# 10X_SD_CARD_READER_SCH_SHEET_1.net
KiCad netlist of a schematic drawn in Altium Designer
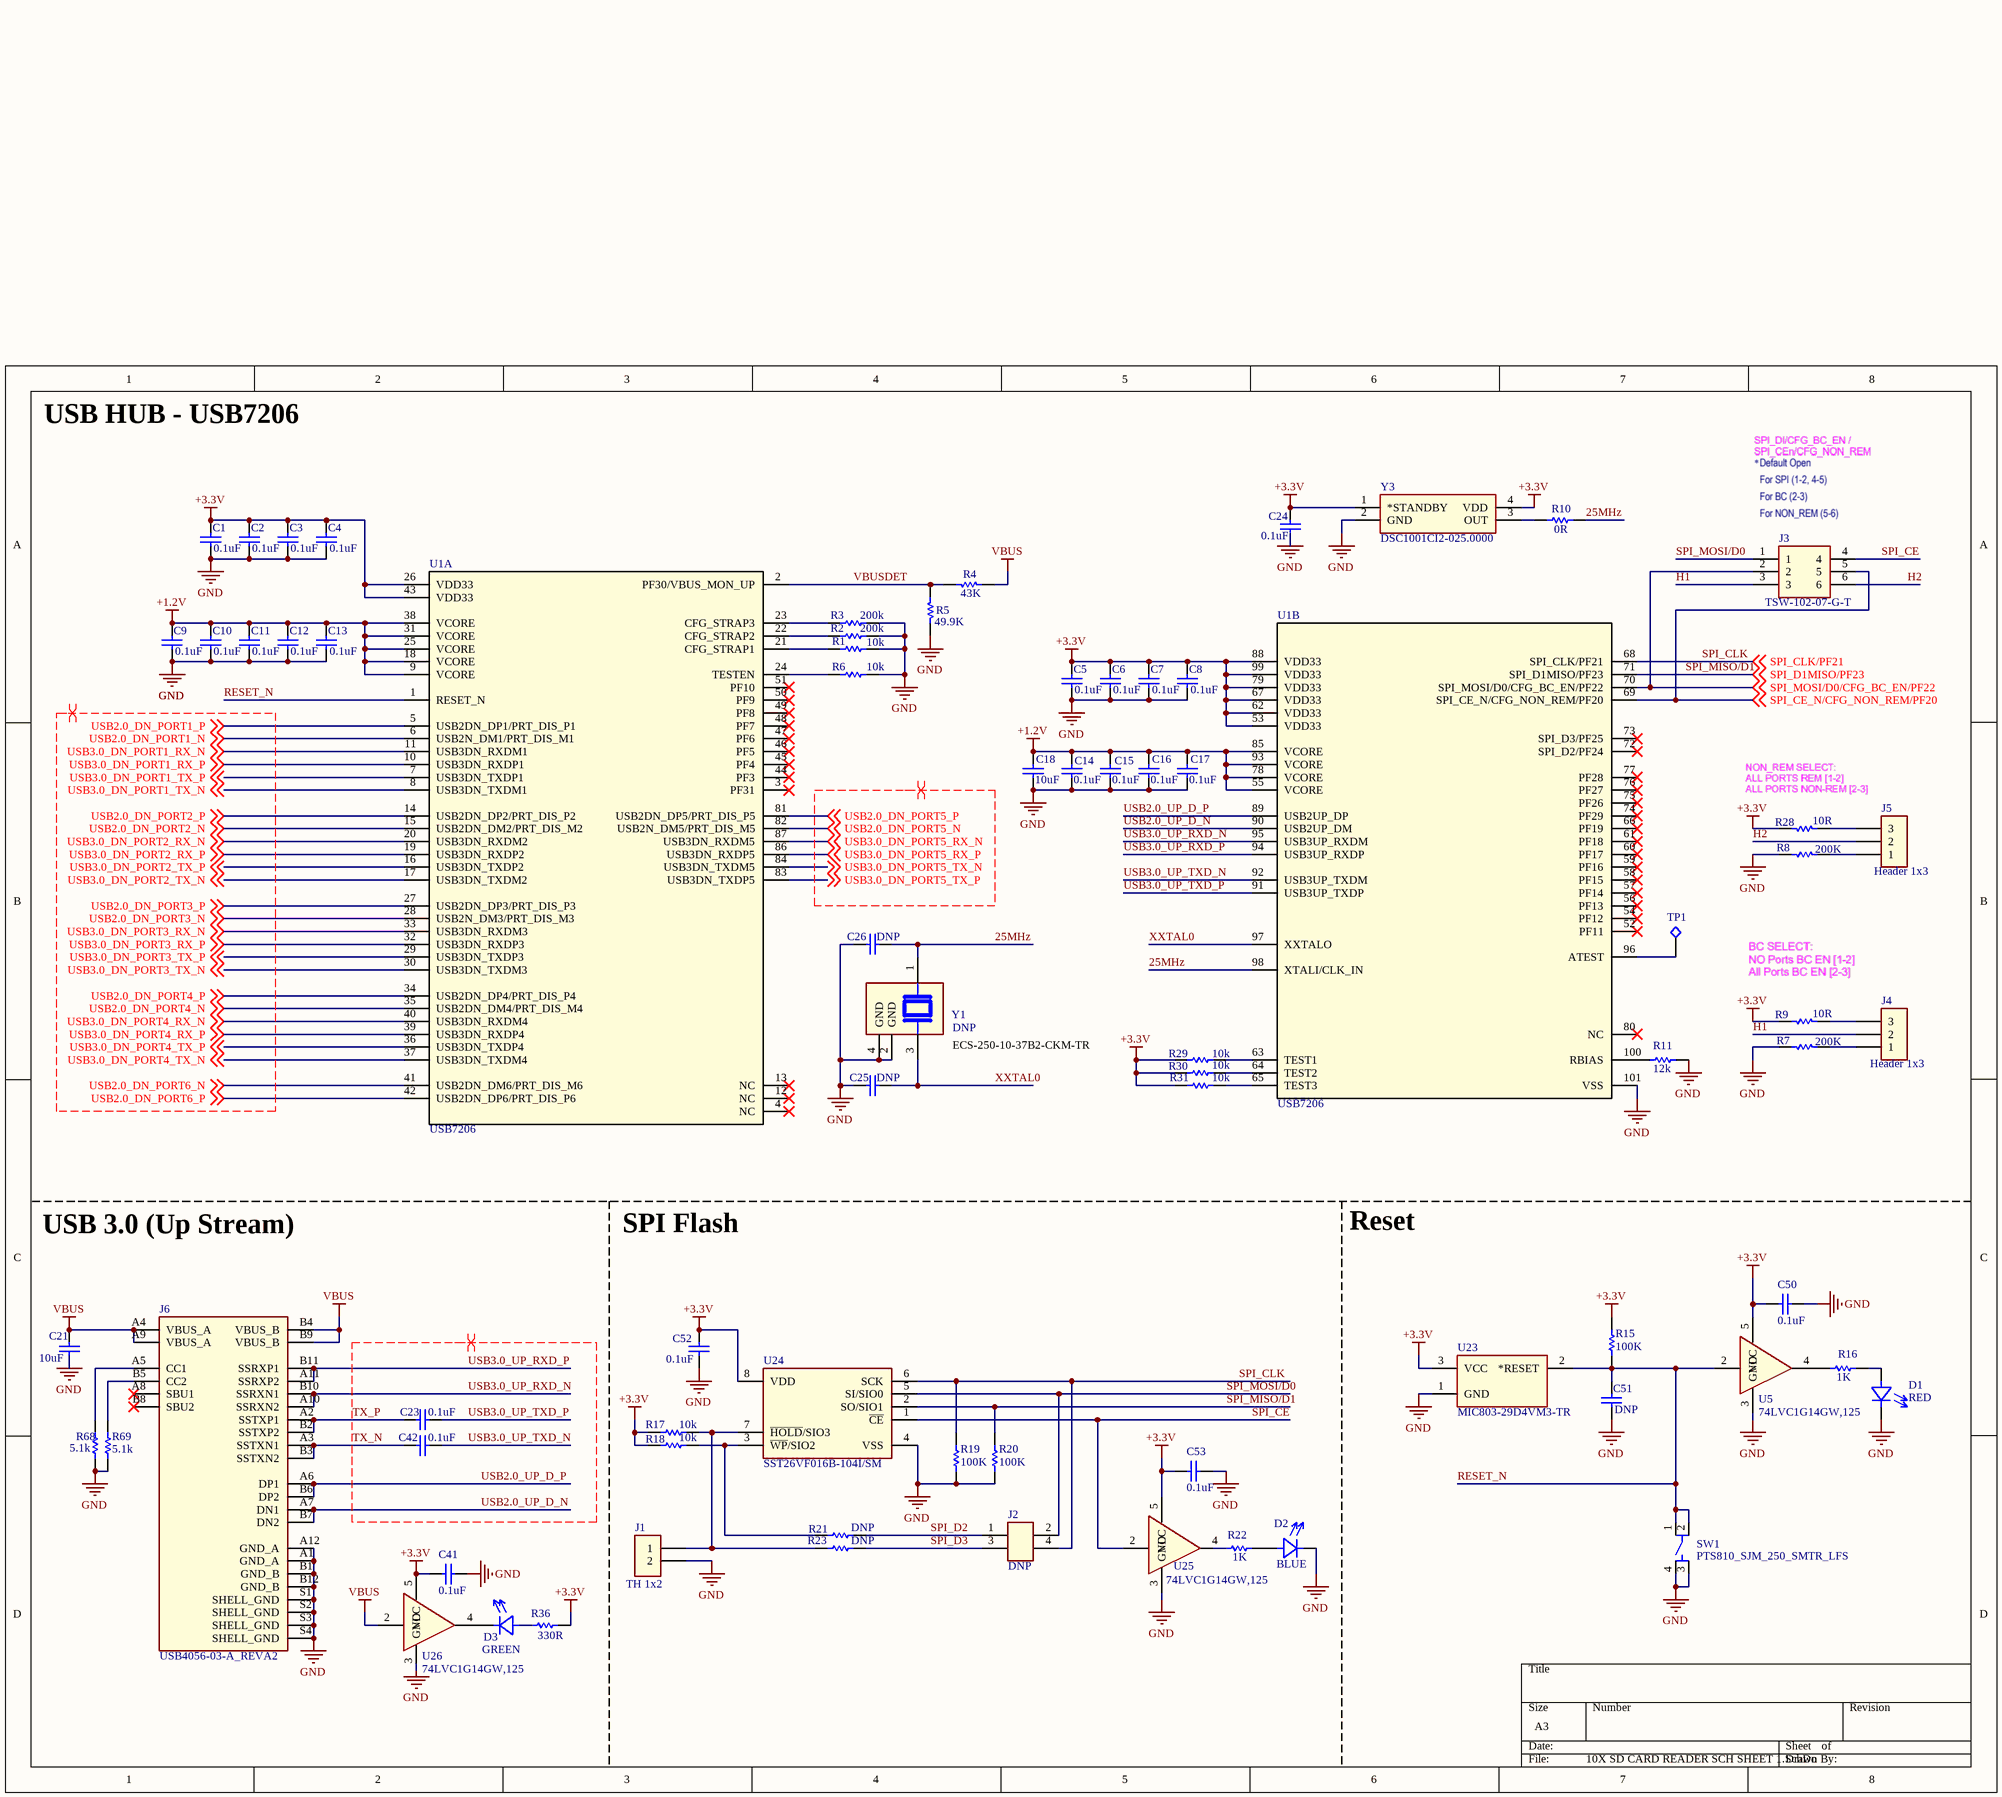
[diagram p0: 10X SD CARD READER SCH SHEET 1.SchDoc]

(export (version "E")
  (design (tool "Eeschema 10.0.6"))
  (components
    (comp (ref "C1")
      (value "0.1uF")
      (footprint "C-0402/1005")
      (description "Capacitor")
      (fields (field (name "PUBLISHER") "Altium Limited"))
      (libsource (lib "Miscellaneous Devices") (part "Cap"))
    )
    (comp (ref "C2")
      (value "0.1uF")
      (footprint "C-0402/1005")
      (description "Capacitor")
      (fields (field (name "PUBLISHER") "Altium Limited"))
      (libsource (lib "Miscellaneous Devices") (part "Cap"))
    )
    (comp (ref "C3")
      (value "0.1uF")
      (footprint "C-0402/1005")
      (description "Capacitor")
      (fields (field (name "PUBLISHER") "Altium Limited"))
      (libsource (lib "Miscellaneous Devices") (part "Cap"))
    )
    (comp (ref "C4")
      (value "0.1uF")
      (footprint "C-0402/1005")
      (description "Capacitor")
      (fields (field (name "PUBLISHER") "Altium Limited"))
      (libsource (lib "Miscellaneous Devices") (part "Cap"))
    )
    (comp (ref "C5")
      (value "0.1uF")
      (footprint "C-0402/1005")
      (description "Capacitor")
      (fields (field (name "PUBLISHER") "Altium Limited"))
      (libsource (lib "Miscellaneous Devices") (part "Cap"))
    )
    (comp (ref "C6")
      (value "0.1uF")
      (footprint "C-0402/1005")
      (description "Capacitor")
      (fields (field (name "PUBLISHER") "Altium Limited"))
      (libsource (lib "Miscellaneous Devices") (part "Cap"))
    )
    (comp (ref "C7")
      (value "0.1uF")
      (footprint "C-0402/1005")
      (description "Capacitor")
      (fields (field (name "PUBLISHER") "Altium Limited"))
      (libsource (lib "Miscellaneous Devices") (part "Cap"))
    )
    (comp (ref "C8")
      (value "0.1uF")
      (footprint "C-0402/1005")
      (description "Capacitor")
      (fields (field (name "PUBLISHER") "Altium Limited"))
      (libsource (lib "Miscellaneous Devices") (part "Cap"))
    )
    (comp (ref "C9")
      (value "0.1uF")
      (footprint "C-0402/1005")
      (description "Capacitor")
      (fields (field (name "PUBLISHER") "Altium Limited"))
      (libsource (lib "Miscellaneous Devices") (part "Cap"))
    )
    (comp (ref "C10")
      (value "0.1uF")
      (footprint "C-0402/1005")
      (description "Capacitor")
      (fields (field (name "PUBLISHER") "Altium Limited"))
      (libsource (lib "Miscellaneous Devices") (part "Cap"))
    )
    (comp (ref "C11")
      (value "0.1uF")
      (footprint "C-0402/1005")
      (description "Capacitor")
      (fields (field (name "PUBLISHER") "Altium Limited"))
      (libsource (lib "Miscellaneous Devices") (part "Cap"))
    )
    (comp (ref "C12")
      (value "0.1uF")
      (footprint "C-0402/1005")
      (description "Capacitor")
      (fields (field (name "PUBLISHER") "Altium Limited"))
      (libsource (lib "Miscellaneous Devices") (part "Cap"))
    )
    (comp (ref "C13")
      (value "0.1uF")
      (footprint "C-0402/1005")
      (description "Capacitor")
      (fields (field (name "PUBLISHER") "Altium Limited"))
      (libsource (lib "Miscellaneous Devices") (part "Cap"))
    )
    (comp (ref "C14")
      (value "0.1uF")
      (footprint "C-0402/1005")
      (description "Capacitor")
      (fields (field (name "PUBLISHER") "Altium Limited"))
      (libsource (lib "Miscellaneous Devices") (part "Cap"))
    )
    (comp (ref "C15")
      (value "0.1uF")
      (footprint "C-0402/1005")
      (description "Capacitor")
      (fields (field (name "PUBLISHER") "Altium Limited"))
      (libsource (lib "Miscellaneous Devices") (part "Cap"))
    )
    (comp (ref "C16")
      (value "0.1uF")
      (footprint "C-0402/1005")
      (description "Capacitor")
      (fields (field (name "PUBLISHER") "Altium Limited"))
      (libsource (lib "Miscellaneous Devices") (part "Cap"))
    )
    (comp (ref "C17")
      (value "0.1uF")
      (footprint "C-0402/1005")
      (description "Capacitor")
      (fields (field (name "PUBLISHER") "Altium Limited"))
      (libsource (lib "Miscellaneous Devices") (part "Cap"))
    )
    (comp (ref "C18")
      (value "10uF")
      (footprint "C-0805/2012")
      (description "Capacitor")
      (fields (field (name "PUBLISHER") "Altium Limited"))
      (libsource (lib "Miscellaneous Devices") (part "Cap"))
    )
    (comp (ref "C21")
      (value "10uF")
      (footprint "C-0805/2012")
      (description "Capacitor")
      (fields (field (name "PUBLISHER") "Altium Limited"))
      (libsource (lib "Miscellaneous Devices") (part "Cap"))
    )
    (comp (ref "C23")
      (value "0.1uF")
      (footprint "C-0402/1005")
      (description "Capacitor")
      (fields (field (name "PUBLISHER") "Altium Limited"))
      (libsource (lib "Miscellaneous Devices") (part "Cap"))
    )
    (comp (ref "C24")
      (value "0.1uF")
      (footprint "C-0402/1005")
      (description "Capacitor")
      (fields (field (name "PUBLISHER") "Altium Limited"))
      (libsource (lib "Miscellaneous Devices") (part "Cap"))
    )
    (comp (ref "C25")
      (value "DNP")
      (footprint "R-0402/1005")
      (description "Capacitor")
      (fields (field (name "PUBLISHER") "Altium Limited"))
      (libsource (lib "Miscellaneous Devices") (part "Cap"))
    )
    (comp (ref "C26")
      (value "DNP")
      (footprint "R-0402/1005")
      (description "Capacitor")
      (fields (field (name "PUBLISHER") "Altium Limited"))
      (libsource (lib "Miscellaneous Devices") (part "Cap"))
    )
    (comp (ref "C41")
      (value "0.1uF")
      (footprint "C-0402/1005")
      (description "Capacitor")
      (fields (field (name "PUBLISHER") "Altium Limited"))
      (libsource (lib "Miscellaneous Devices") (part "Cap"))
    )
    (comp (ref "C42")
      (value "0.1uF")
      (footprint "C-0402/1005")
      (description "Capacitor")
      (fields (field (name "PUBLISHER") "Altium Limited"))
      (libsource (lib "Miscellaneous Devices") (part "Cap"))
    )
    (comp (ref "C50")
      (value "0.1uF")
      (footprint "C-0402/1005")
      (description "Capacitor")
      (fields (field (name "PUBLISHER") "Altium Limited"))
      (libsource (lib "Miscellaneous Devices") (part "Cap"))
    )
    (comp (ref "C51")
      (value "DNP")
      (footprint "C-0402/1005")
      (description "Capacitor")
      (fields (field (name "Comment") "0.1uF") (field (name "PUBLISHER") "Altium Limited"))
      (libsource (lib "Miscellaneous Devices") (part "Cap"))
    )
    (comp (ref "C52")
      (value "0.1uF")
      (footprint "C-0402/1005")
      (description "Capacitor")
      (fields (field (name "PUBLISHER") "Altium Limited"))
      (libsource (lib "Miscellaneous Devices") (part "Cap"))
    )
    (comp (ref "C53")
      (value "0.1uF")
      (footprint "C-0402/1005")
      (description "Capacitor")
      (fields (field (name "PUBLISHER") "Altium Limited"))
      (libsource (lib "Miscellaneous Devices") (part "Cap"))
    )
    (comp (ref "D1")
      (value "RED")
      (footprint "LEDC1608X65N")
      (libsource (lib "Custom_Library") (part "Diode-LED"))
    )
    (comp (ref "D2")
      (value "BLUE")
      (footprint "LEDC1608X65N")
      (libsource (lib "Custom_Library") (part "Diode-LED"))
    )
    (comp (ref "D3")
      (value "GREEN")
      (footprint "LEDC1608X65N")
      (libsource (lib "Custom_Library") (part "Diode-LED"))
    )
    (comp (ref "J1")
      (value "TH 1x2")
      (footprint "PIN HEADER 1x2 2.54mm")
      (description "CONN HEADER VERT 3POS 2.54MM")
      (fields (field (name "MFR. PART NO.") "75160-156-03LF"))
      (libsource (lib "Custom_Library") (part "Header 1x2"))
    )
    (comp (ref "J2")
      (value "DNP")
      (footprint "PIN HEADER 2x2 2.54mm")
      (description "FIXED IND 22UH 620MA 350 MOHM")
      (fields (field (name "MFR. PART NO.") "PH2-04-UA"))
      (libsource (lib "Custom_Library") (part "Header 2x2"))
    )
    (comp (ref "J3")
      (value "TSW-102-07-G-T")
      (footprint "CON6_3X2_TU_TSW_SAI")
      (description "No Description Available")
      (fields (field (name "COPYRIGHT") "Copyright (C) 2023 Ultra Librarian. All rights reserved."))
      (libsource (lib "TSW-102-07-G-T") (part "TSW-102-07-G-T"))
    )
    (comp (ref "J4")
      (value "Header 1x3")
      (footprint "PIN HEADER 1x3 2.54mm")
      (description "CONN HEADER VERT 3POS 2.54MM")
      (fields (field (name "MFR. PART NO.") "75160-156-03LF"))
      (libsource (lib "Custom_Library") (part "Header 1x3"))
    )
    (comp (ref "J5")
      (value "Header 1x3")
      (footprint "PIN HEADER 1x3 2.54mm")
      (description "CONN HEADER VERT 3POS 2.54MM")
      (fields (field (name "MFR. PART NO.") "75160-156-03LF"))
      (libsource (lib "Custom_Library") (part "Header 1x3"))
    )
    (comp (ref "J6")
      (value "USB4056-03-A_REVA2")
      (footprint "GCT_USB4056-03-A_REVA2")
      (fields (field (name "MF") "Global Connector Technology") (field (name "MP") "USB4056-03-A"))
      (libsource (lib "USB4056-03-A_REVA2") (part "USB4056-03-A_REVA2"))
    )
    (comp (ref "R1")
      (value "10k")
      (footprint "R-0402/1005")
      (description "Resistor")
      (fields (field (name "PUBLISHER") "Altium Limited"))
      (libsource (lib "Miscellaneous Devices") (part "Res1"))
    )
    (comp (ref "R2")
      (value "200k")
      (footprint "R-0402/1005")
      (description "Resistor")
      (fields (field (name "PUBLISHER") "Altium Limited"))
      (libsource (lib "Miscellaneous Devices") (part "Res1"))
    )
    (comp (ref "R3")
      (value "200k")
      (footprint "R-0402/1005")
      (description "Resistor")
      (fields (field (name "PUBLISHER") "Altium Limited"))
      (libsource (lib "Miscellaneous Devices") (part "Res1"))
    )
    (comp (ref "R4")
      (value "43K")
      (footprint "R-0402/1005")
      (description "Resistor")
      (fields (field (name "PUBLISHER") "Altium Limited"))
      (libsource (lib "Miscellaneous Devices") (part "Res1"))
    )
    (comp (ref "R5")
      (value "49.9K")
      (footprint "R-0402/1005")
      (description "Resistor")
      (fields (field (name "PUBLISHER") "Altium Limited"))
      (libsource (lib "Miscellaneous Devices") (part "Res1"))
    )
    (comp (ref "R6")
      (value "10k")
      (footprint "R-0402/1005")
      (description "Resistor")
      (fields (field (name "PUBLISHER") "Altium Limited"))
      (libsource (lib "Miscellaneous Devices") (part "Res1"))
    )
    (comp (ref "R7")
      (value "200K")
      (footprint "R-0402/1005")
      (description "Resistor")
      (fields (field (name "PUBLISHER") "Altium Limited"))
      (libsource (lib "Miscellaneous Devices") (part "Res1"))
    )
    (comp (ref "R8")
      (value "200K")
      (footprint "R-0402/1005")
      (description "Resistor")
      (fields (field (name "PUBLISHER") "Altium Limited"))
      (libsource (lib "Miscellaneous Devices") (part "Res1"))
    )
    (comp (ref "R9")
      (value "10R")
      (footprint "R-0402/1005")
      (description "Resistor")
      (fields (field (name "PUBLISHER") "Altium Limited"))
      (libsource (lib "Miscellaneous Devices") (part "Res1"))
    )
    (comp (ref "R10")
      (value "0R")
      (footprint "R-0402/1005")
      (description "Resistor")
      (fields (field (name "PUBLISHER") "Altium Limited"))
      (libsource (lib "Miscellaneous Devices") (part "Res1"))
    )
    (comp (ref "R11")
      (value "12k")
      (footprint "R-0402/1005")
      (description "Resistor")
      (fields (field (name "PUBLISHER") "Altium Limited"))
      (libsource (lib "Miscellaneous Devices") (part "Res1"))
    )
    (comp (ref "R15")
      (value "100K")
      (footprint "R-0402/1005")
      (description "Resistor")
      (fields (field (name "PUBLISHER") "Altium Limited"))
      (libsource (lib "Miscellaneous Devices") (part "Res1"))
    )
    (comp (ref "R16")
      (value "1K")
      (footprint "R-0402/1005")
      (description "Resistor")
      (fields (field (name "PUBLISHER") "Altium Limited"))
      (libsource (lib "Miscellaneous Devices") (part "Res1"))
    )
    (comp (ref "R17")
      (value "10k")
      (footprint "R-0402/1005")
      (description "Resistor")
      (fields (field (name "PUBLISHER") "Altium Limited"))
      (libsource (lib "Miscellaneous Devices") (part "Res1"))
    )
    (comp (ref "R18")
      (value "10k")
      (footprint "R-0402/1005")
      (description "Resistor")
      (fields (field (name "PUBLISHER") "Altium Limited"))
      (libsource (lib "Miscellaneous Devices") (part "Res1"))
    )
    (comp (ref "R19")
      (value "100K")
      (footprint "R-0402/1005")
      (description "Resistor")
      (fields (field (name "PUBLISHER") "Altium Limited"))
      (libsource (lib "Miscellaneous Devices") (part "Res1"))
    )
    (comp (ref "R20")
      (value "100K")
      (footprint "R-0402/1005")
      (description "Resistor")
      (fields (field (name "PUBLISHER") "Altium Limited"))
      (libsource (lib "Miscellaneous Devices") (part "Res1"))
    )
    (comp (ref "R21")
      (value "DNP")
      (footprint "R-0402/1005")
      (description "Resistor")
      (fields (field (name "PUBLISHER") "Altium Limited"))
      (libsource (lib "Miscellaneous Devices") (part "Res1"))
    )
    (comp (ref "R22")
      (value "1K")
      (footprint "R-0402/1005")
      (description "Resistor")
      (fields (field (name "PUBLISHER") "Altium Limited"))
      (libsource (lib "Miscellaneous Devices") (part "Res1"))
    )
    (comp (ref "R23")
      (value "DNP")
      (footprint "R-0402/1005")
      (description "Resistor")
      (fields (field (name "PUBLISHER") "Altium Limited"))
      (libsource (lib "Miscellaneous Devices") (part "Res1"))
    )
    (comp (ref "R28")
      (value "10R")
      (footprint "R-0402/1005")
      (description "Resistor")
      (fields (field (name "PUBLISHER") "Altium Limited"))
      (libsource (lib "Miscellaneous Devices") (part "Res1"))
    )
    (comp (ref "R29")
      (value "10k")
      (footprint "R-0402/1005")
      (description "Resistor")
      (fields (field (name "PUBLISHER") "Altium Limited"))
      (libsource (lib "Miscellaneous Devices") (part "Res1"))
    )
    (comp (ref "R30")
      (value "10k")
      (footprint "R-0402/1005")
      (description "Resistor")
      (fields (field (name "PUBLISHER") "Altium Limited"))
      (libsource (lib "Miscellaneous Devices") (part "Res1"))
    )
    (comp (ref "R31")
      (value "10k")
      (footprint "R-0402/1005")
      (description "Resistor")
      (fields (field (name "PUBLISHER") "Altium Limited"))
      (libsource (lib "Miscellaneous Devices") (part "Res1"))
    )
    (comp (ref "R36")
      (value "330R")
      (footprint "R-0402/1005")
      (description "Resistor")
      (fields (field (name "PUBLISHER") "Altium Limited"))
      (libsource (lib "Miscellaneous Devices") (part "Res1"))
    )
    (comp (ref "R68")
      (value "5.1k")
      (footprint "R-0402/1005")
      (description "Resistor")
      (fields (field (name "PUBLISHER") "Altium Limited"))
      (libsource (lib "Miscellaneous Devices") (part "Res1"))
    )
    (comp (ref "R69")
      (value "5.1k")
      (footprint "R-0402/1005")
      (description "Resistor")
      (fields (field (name "PUBLISHER") "Altium Limited"))
      (libsource (lib "Miscellaneous Devices") (part "Res1"))
    )
    (comp (ref "SW1")
      (value "PTS810_SJM_250_SMTR_LFS")
      (footprint "SW_PTS810_SJM_250_SMTR_LFS")
      (description "Tactile Switch SPST-NO Top Actuated Surface Mount")
      (fields (field (name "MF") "C&K") (field (name "MP") "PTS810 SJM 250 SMTR LFS"))
      (libsource (lib "PTS810_SJM_250_SMTR_LFS") (part "PTS810_SJM_250_SMTR_LFS"))
    )
    (comp (ref "TP1")
      (value "Test Points")
      (footprint "Test Point TH Round H0.9,D1.6")
      (libsource (lib "Custom_Library") (part "Test Points"))
    )
    (comp (ref "U1")
      (value "USB7206")
      (footprint "USB7206")
      (description "IC USB3.1 GEN2 HUB TYPE C")
      (fields
        (field (name "MANUFACTURER") "Microchip Technology")
        (field (name "DIGI-KEY PART NUMBER") "150-USB7206CT-I/KDXTR-ND")
      )
      (libsource (lib "10X SD CARD READER SCH LIB") (part "USB7206"))
    )
    (comp (ref "U5")
      (value "74LVC1G14GW,125")
      (footprint "SOT65P212X110-5N")
      (description "Inverter Schmitt Trigger 1-Element CMOS 5-Pin TSSOP T/R")
      (libsource (lib "74LVC1G14GW,125") (part "74LVC1G14GW,125"))
    )
    (comp (ref "U23")
      (value "MIC803-29D4VM3-TR")
      (footprint "SOT-23_M3_MCH")
      (description "No Description Available")
      (fields (field (name "COPYRIGHT") "Copyright (C) 2023 Ultra Librarian. All rights reserved."))
      (libsource (lib "MIC803-29D4VM3-TR") (part "MIC803-29D4VM3-TR"))
    )
    (comp (ref "U24")
      (value "SST26VF016B-104I/SM")
      (footprint "SOIC127P794X203-8N")
      (libsource (lib "10X SD CARD READER SCH LIB") (part "SST26VF016B-104I/SM"))
    )
    (comp (ref "U25")
      (value "74LVC1G14GW,125")
      (footprint "SOT65P212X110-5N")
      (description "Inverter Schmitt Trigger 1-Element CMOS 5-Pin TSSOP T/R")
      (libsource (lib "74LVC1G14GW,125") (part "74LVC1G14GW,125"))
    )
    (comp (ref "U26")
      (value "74LVC1G14GW,125")
      (footprint "SOT65P212X110-5N")
      (description "Inverter Schmitt Trigger 1-Element CMOS 5-Pin TSSOP T/R")
      (libsource (lib "74LVC1G14GW,125") (part "74LVC1G14GW,125"))
    )
    (comp (ref "Y1")
      (value "DNP")
      (footprint "ECS-250-10-37B2")
      (libsource (lib "10X SD CARD READER SCH LIB") (part "ECS-250-10-37B2-CKM-TR"))
    )
    (comp (ref "Y3")
      (value "DSC1001CI2-025.0000")
      (footprint "CDFN4_3P2X2P5_MCH")
      (description "No Description Available")
      (fields (field (name "COPYRIGHT") "Copyright (C) 2023 Ultra Librarian. All rights reserved."))
      (libsource (lib "DSC1001CI2-025P0000") (part "DSC1001CI2-025.0000"))
    )
  )
  (nets
    (net (code "1") (name "+1.2V") (class "Default")
      (node (ref "C10") (pin "2") (pinfunction "2_2") (pintype "passive"))
      (node (ref "C11") (pin "2") (pinfunction "2_2") (pintype "passive"))
      (node (ref "C12") (pin "2") (pinfunction "2_2") (pintype "passive"))
      (node (ref "C13") (pin "2") (pinfunction "2_2") (pintype "passive"))
      (node (ref "C14") (pin "1") (pinfunction "1_1") (pintype "passive"))
      (node (ref "C15") (pin "1") (pinfunction "1_1") (pintype "passive"))
      (node (ref "C16") (pin "2") (pinfunction "2_2") (pintype "passive"))
      (node (ref "C17") (pin "2") (pinfunction "2_2") (pintype "passive"))
      (node (ref "C18") (pin "2") (pinfunction "2_2") (pintype "passive"))
      (node (ref "C9") (pin "2") (pinfunction "2_2") (pintype "passive"))
      (node (ref "U1") (pin "18") (pinfunction "VCORE_18") (pintype "passive"))
      (node (ref "U1") (pin "25") (pinfunction "VCORE_25") (pintype "passive"))
      (node (ref "U1") (pin "31") (pinfunction "VCORE_31") (pintype "passive"))
      (node (ref "U1") (pin "38") (pinfunction "VCORE_38") (pintype "passive"))
      (node (ref "U1") (pin "55") (pinfunction "VCORE_55") (pintype "passive"))
      (node (ref "U1") (pin "78") (pinfunction "VCORE_78") (pintype "passive"))
      (node (ref "U1") (pin "85") (pinfunction "VCORE_85") (pintype "passive"))
      (node (ref "U1") (pin "9") (pinfunction "VCORE_9") (pintype "passive"))
      (node (ref "U1") (pin "93") (pinfunction "VCORE_93") (pintype "passive"))
    )
    (net (code "2") (name "+3.3V") (class "Default")
      (node (ref "C1") (pin "2") (pinfunction "2_2") (pintype "passive"))
      (node (ref "C2") (pin "2") (pinfunction "2_2") (pintype "passive"))
      (node (ref "C24") (pin "2") (pinfunction "2_2") (pintype "passive"))
      (node (ref "C3") (pin "2") (pinfunction "2_2") (pintype "passive"))
      (node (ref "C4") (pin "2") (pinfunction "2_2") (pintype "passive"))
      (node (ref "C41") (pin "2") (pinfunction "2_2") (pintype "passive"))
      (node (ref "C5") (pin "2") (pinfunction "2_2") (pintype "passive"))
      (node (ref "C50") (pin "2") (pinfunction "2_2") (pintype "passive"))
      (node (ref "C52") (pin "2") (pinfunction "2_2") (pintype "passive"))
      (node (ref "C53") (pin "2") (pinfunction "2_2") (pintype "passive"))
      (node (ref "C6") (pin "2") (pinfunction "2_2") (pintype "passive"))
      (node (ref "C7") (pin "2") (pinfunction "2_2") (pintype "passive"))
      (node (ref "C8") (pin "2") (pinfunction "2_2") (pintype "passive"))
      (node (ref "R15") (pin "1") (pinfunction "1_1") (pintype "passive"))
      (node (ref "R17") (pin "2") (pinfunction "2_2") (pintype "passive"))
      (node (ref "R18") (pin "2") (pinfunction "2_2") (pintype "passive"))
      (node (ref "R28") (pin "2") (pinfunction "2_2") (pintype "passive"))
      (node (ref "R29") (pin "2") (pinfunction "2_2") (pintype "passive"))
      (node (ref "R30") (pin "2") (pinfunction "2_2") (pintype "passive"))
      (node (ref "R31") (pin "2") (pinfunction "2_2") (pintype "passive"))
      (node (ref "R36") (pin "2") (pinfunction "2_2") (pintype "passive"))
      (node (ref "R9") (pin "2") (pinfunction "2_2") (pintype "passive"))
      (node (ref "U1") (pin "26") (pinfunction "VDD33_26") (pintype "passive"))
      (node (ref "U1") (pin "43") (pinfunction "VDD33_43") (pintype "passive"))
      (node (ref "U1") (pin "53") (pinfunction "VDD33_53") (pintype "passive"))
      (node (ref "U1") (pin "62") (pinfunction "VDD33_62") (pintype "passive"))
      (node (ref "U1") (pin "67") (pinfunction "VDD33_67") (pintype "passive"))
      (node (ref "U1") (pin "79") (pinfunction "VDD33_79") (pintype "passive"))
      (node (ref "U1") (pin "88") (pinfunction "VDD33_88") (pintype "passive"))
      (node (ref "U1") (pin "99") (pinfunction "VDD33_99") (pintype "passive"))
      (node (ref "U23") (pin "3") (pinfunction "VCC_3") (pintype "power_in"))
      (node (ref "U24") (pin "8") (pinfunction "VDD_8") (pintype "passive"))
      (node (ref "U25") (pin "5") (pinfunction "VCC_5") (pintype "passive"))
      (node (ref "U26") (pin "5") (pinfunction "VCC_5") (pintype "passive"))
      (node (ref "U5") (pin "5") (pinfunction "VCC_5") (pintype "passive"))
      (node (ref "Y3") (pin "1") (pinfunction "*STANDBY_1") (pintype "passive"))
      (node (ref "Y3") (pin "4") (pinfunction "VDD_4") (pintype "passive"))
    )
    (net (code "3") (name "/25MHz") (class "Default")
      (node (ref "C26") (pin "1") (pinfunction "1_1") (pintype "passive"))
      (node (ref "R10") (pin "2") (pinfunction "2_2") (pintype "passive"))
      (node (ref "U1") (pin "98") (pinfunction "XTALI/CLK_IN_98") (pintype "passive"))
      (node (ref "Y1") (pin "1") (pinfunction "1_1") (pintype "passive"))
    )
    (net (code "4") (name "/H1") (class "Default")
      (node (ref "J3") (pin "3") (pinfunction "3_3") (pintype "passive"))
      (node (ref "J4") (pin "2") (pinfunction "2_2") (pintype "passive"))
    )
    (net (code "5") (name "/H2") (class "Default")
      (node (ref "J3") (pin "6") (pinfunction "6_6") (pintype "passive"))
      (node (ref "J5") (pin "2") (pinfunction "2_2") (pintype "passive"))
    )
    (net (code "6") (name "/RESET_N") (class "Default")
      (node (ref "C51") (pin "2") (pinfunction "2_2") (pintype "passive"))
      (node (ref "R15") (pin "2") (pinfunction "2_2") (pintype "passive"))
      (node (ref "SW1") (pin "1") (pinfunction "1_1") (pintype "passive"))
      (node (ref "SW1") (pin "2") (pinfunction "2_2") (pintype "passive"))
      (node (ref "U1") (pin "1") (pinfunction "RESET_N_1") (pintype "passive"))
      (node (ref "U23") (pin "2") (pinfunction "*RESET_2") (pintype "passive"))
      (node (ref "U5") (pin "2") (pinfunction "A_2") (pintype "passive"))
    )
    (net (code "7") (name "/SPI_CE") (class "Default")
      (node (ref "J3") (pin "4") (pinfunction "4_4") (pintype "passive"))
      (node (ref "U24") (pin "1") (pinfunction "~{CE}_1") (pintype "passive"))
      (node (ref "U25") (pin "2") (pinfunction "A_2") (pintype "passive"))
    )
    (net (code "8") (name "/SPI_D2") (class "Default")
      (node (ref "J2") (pin "1") (pinfunction "1_1") (pintype "passive"))
      (node (ref "R21") (pin "2") (pinfunction "2_2") (pintype "passive"))
    )
    (net (code "9") (name "/SPI_D3") (class "Default")
      (node (ref "J2") (pin "3") (pinfunction "3_3") (pintype "passive"))
      (node (ref "R23") (pin "2") (pinfunction "2_2") (pintype "passive"))
    )
    (net (code "10") (name "/SPI_MOSI{slash}D0") (class "Default")
      (node (ref "J2") (pin "2") (pinfunction "2_2") (pintype "passive"))
      (node (ref "J3") (pin "1") (pinfunction "1_1") (pintype "passive"))
      (node (ref "U24") (pin "5") (pinfunction "SI/SIO0_5") (pintype "passive"))
    )
    (net (code "11") (name "/TX_N") (class "Default")
      (node (ref "C42") (pin "2") (pinfunction "2_2") (pintype "passive"))
      (node (ref "J6") (pin "A3") (pinfunction "SSTXN1_A3") (pintype "passive"))
      (node (ref "J6") (pin "B3") (pinfunction "SSTXN2_B3") (pintype "passive"))
    )
    (net (code "12") (name "/TX_P") (class "Default")
      (node (ref "C23") (pin "2") (pinfunction "2_2") (pintype "passive"))
      (node (ref "J6") (pin "A2") (pinfunction "SSTXP1_A2") (pintype "passive"))
      (node (ref "J6") (pin "B2") (pinfunction "SSTXP2_B2") (pintype "passive"))
    )
    (net (code "13") (name "/USB2.0_UP_D_N") (class "Default")
      (node (ref "J6") (pin "A7") (pinfunction "DN1_A7") (pintype "passive"))
      (node (ref "J6") (pin "B7") (pinfunction "DN2_B7") (pintype "passive"))
      (node (ref "U1") (pin "90") (pinfunction "USB2UP_DM_90") (pintype "passive"))
    )
    (net (code "14") (name "/USB2.0_UP_D_P") (class "Default")
      (node (ref "J6") (pin "A6") (pinfunction "DP1_A6") (pintype "passive"))
      (node (ref "J6") (pin "B6") (pinfunction "DP2_B6") (pintype "passive"))
      (node (ref "U1") (pin "89") (pinfunction "USB2UP_DP_89") (pintype "passive"))
    )
    (net (code "15") (name "/USB3.0_UP_RXD_N") (class "Default")
      (node (ref "J6") (pin "A10") (pinfunction "SSRXN2_A10") (pintype "passive"))
      (node (ref "J6") (pin "B10") (pinfunction "SSRXN1_B10") (pintype "passive"))
      (node (ref "U1") (pin "95") (pinfunction "USB3UP_RXDM_95") (pintype "passive"))
    )
    (net (code "16") (name "/USB3.0_UP_RXD_P") (class "Default")
      (node (ref "J6") (pin "A11") (pinfunction "SSRXP2_A11") (pintype "passive"))
      (node (ref "J6") (pin "B11") (pinfunction "SSRXP1_B11") (pintype "passive"))
      (node (ref "U1") (pin "94") (pinfunction "USB3UP_RXDP_94") (pintype "passive"))
    )
    (net (code "17") (name "/USB3.0_UP_TXD_N") (class "Default")
      (node (ref "C42") (pin "1") (pinfunction "1_1") (pintype "passive"))
      (node (ref "U1") (pin "92") (pinfunction "USB3UP_TXDM_92") (pintype "passive"))
    )
    (net (code "18") (name "/USB3.0_UP_TXD_P") (class "Default")
      (node (ref "C23") (pin "1") (pinfunction "1_1") (pintype "passive"))
      (node (ref "U1") (pin "91") (pinfunction "USB3UP_TXDP_91") (pintype "passive"))
    )
    (net (code "19") (name "/VBUSDET") (class "Default")
      (node (ref "R4") (pin "1") (pinfunction "1_1") (pintype "passive"))
      (node (ref "R5") (pin "1") (pinfunction "1_1") (pintype "passive"))
      (node (ref "U1") (pin "2") (pinfunction "PF30/VBUS_MON_UP_2") (pintype "passive"))
    )
    (net (code "20") (name "/XXTAL0") (class "Default")
      (node (ref "C25") (pin "1") (pinfunction "1_1") (pintype "passive"))
      (node (ref "U1") (pin "97") (pinfunction "XXTALO_97") (pintype "passive"))
      (node (ref "Y1") (pin "3") (pinfunction "2_3") (pintype "passive"))
    )
    (net (code "21") (name "GND") (class "Default")
      (node (ref "C1") (pin "1") (pinfunction "1_1") (pintype "passive"))
      (node (ref "C10") (pin "1") (pinfunction "1_1") (pintype "passive"))
      (node (ref "C11") (pin "1") (pinfunction "1_1") (pintype "passive"))
      (node (ref "C12") (pin "1") (pinfunction "1_1") (pintype "passive"))
      (node (ref "C13") (pin "1") (pinfunction "1_1") (pintype "passive"))
      (node (ref "C14") (pin "2") (pinfunction "2_2") (pintype "passive"))
      (node (ref "C15") (pin "2") (pinfunction "2_2") (pintype "passive"))
      (node (ref "C16") (pin "1") (pinfunction "1_1") (pintype "passive"))
      (node (ref "C17") (pin "1") (pinfunction "1_1") (pintype "passive"))
      (node (ref "C18") (pin "1") (pinfunction "1_1") (pintype "passive"))
      (node (ref "C2") (pin "1") (pinfunction "1_1") (pintype "passive"))
      (node (ref "C21") (pin "1") (pinfunction "1_1") (pintype "passive"))
      (node (ref "C24") (pin "1") (pinfunction "1_1") (pintype "passive"))
      (node (ref "C25") (pin "2") (pinfunction "2_2") (pintype "passive"))
      (node (ref "C26") (pin "2") (pinfunction "2_2") (pintype "passive"))
      (node (ref "C3") (pin "1") (pinfunction "1_1") (pintype "passive"))
      (node (ref "C4") (pin "1") (pinfunction "1_1") (pintype "passive"))
      (node (ref "C41") (pin "1") (pinfunction "1_1") (pintype "passive"))
      (node (ref "C5") (pin "1") (pinfunction "1_1") (pintype "passive"))
      (node (ref "C50") (pin "1") (pinfunction "1_1") (pintype "passive"))
      (node (ref "C51") (pin "1") (pinfunction "1_1") (pintype "passive"))
      (node (ref "C52") (pin "1") (pinfunction "1_1") (pintype "passive"))
      (node (ref "C53") (pin "1") (pinfunction "1_1") (pintype "passive"))
      (node (ref "C6") (pin "1") (pinfunction "1_1") (pintype "passive"))
      (node (ref "C7") (pin "1") (pinfunction "1_1") (pintype "passive"))
      (node (ref "C8") (pin "1") (pinfunction "1_1") (pintype "passive"))
      (node (ref "C9") (pin "1") (pinfunction "1_1") (pintype "passive"))
      (node (ref "D1") (pin "C") (pinfunction "C_C") (pintype "passive"))
      (node (ref "D2") (pin "C") (pinfunction "C_C") (pintype "passive"))
      (node (ref "J1") (pin "2") (pinfunction "2_2") (pintype "passive"))
      (node (ref "J6") (pin "A1") (pinfunction "GND_A_A1") (pintype "passive"))
      (node (ref "J6") (pin "A12") (pinfunction "GND_A_A12") (pintype "passive"))
      (node (ref "J6") (pin "B1") (pinfunction "GND_B_B1") (pintype "passive"))
      (node (ref "J6") (pin "B12") (pinfunction "GND_B_B12") (pintype "passive"))
      (node (ref "J6") (pin "S1") (pinfunction "SHELL_GND_S1") (pintype "passive"))
      (node (ref "J6") (pin "S2") (pinfunction "SHELL_GND_S2") (pintype "passive"))
      (node (ref "J6") (pin "S3") (pinfunction "SHELL_GND_S3") (pintype "passive"))
      (node (ref "J6") (pin "S4") (pinfunction "SHELL_GND_S4") (pintype "passive"))
      (node (ref "R1") (pin "2") (pinfunction "2_2") (pintype "passive"))
      (node (ref "R11") (pin "1") (pinfunction "1_1") (pintype "passive"))
      (node (ref "R19") (pin "2") (pinfunction "2_2") (pintype "passive"))
      (node (ref "R2") (pin "2") (pinfunction "2_2") (pintype "passive"))
      (node (ref "R20") (pin "2") (pinfunction "2_2") (pintype "passive"))
      (node (ref "R3") (pin "2") (pinfunction "2_2") (pintype "passive"))
      (node (ref "R5") (pin "2") (pinfunction "2_2") (pintype "passive"))
      (node (ref "R6") (pin "1") (pinfunction "1_1") (pintype "passive"))
      (node (ref "R68") (pin "1") (pinfunction "1_1") (pintype "passive"))
      (node (ref "R69") (pin "1") (pinfunction "1_1") (pintype "passive"))
      (node (ref "R7") (pin "1") (pinfunction "1_1") (pintype "passive"))
      (node (ref "R8") (pin "1") (pinfunction "1_1") (pintype "passive"))
      (node (ref "SW1") (pin "3") (pinfunction "3_3") (pintype "passive"))
      (node (ref "SW1") (pin "4") (pinfunction "4_4") (pintype "passive"))
      (node (ref "U1") (pin "101") (pinfunction "VSS_101") (pintype "passive"))
      (node (ref "U23") (pin "1") (pinfunction "GND_1") (pintype "power_in"))
      (node (ref "U24") (pin "4") (pinfunction "VSS_4") (pintype "passive"))
      (node (ref "U25") (pin "3") (pinfunction "GND_3") (pintype "passive"))
      (node (ref "U26") (pin "3") (pinfunction "GND_3") (pintype "passive"))
      (node (ref "U5") (pin "3") (pinfunction "GND_3") (pintype "passive"))
      (node (ref "Y1") (pin "2") (pinfunction "GND_2") (pintype "power_in"))
      (node (ref "Y1") (pin "4") (pinfunction "GND_4") (pintype "power_in"))
      (node (ref "Y3") (pin "2") (pinfunction "GND_2") (pintype "passive"))
    )
    (net (code "22") (name "Net-(D1-PadA)") (class "Default")
      (node (ref "D1") (pin "A") (pinfunction "A_A") (pintype "passive"))
      (node (ref "R16") (pin "1") (pinfunction "1_1") (pintype "passive"))
    )
    (net (code "23") (name "Net-(D2-PadA)") (class "Default")
      (node (ref "D2") (pin "A") (pinfunction "A_A") (pintype "passive"))
      (node (ref "R22") (pin "1") (pinfunction "1_1") (pintype "passive"))
    )
    (net (code "24") (name "Net-(D3-PadA)") (class "Default")
      (node (ref "D3") (pin "A") (pinfunction "A_A") (pintype "passive"))
      (node (ref "R36") (pin "1") (pinfunction "1_1") (pintype "passive"))
    )
    (net (code "25") (name "Net-(J4-Pad1)") (class "Default")
      (node (ref "J4") (pin "1") (pinfunction "1_1") (pintype "passive"))
      (node (ref "R7") (pin "2") (pinfunction "2_2") (pintype "passive"))
    )
    (net (code "26") (name "Net-(J4-Pad3)") (class "Default")
      (node (ref "J4") (pin "3") (pinfunction "3_3") (pintype "passive"))
      (node (ref "R9") (pin "1") (pinfunction "1_1") (pintype "passive"))
    )
    (net (code "27") (name "Net-(J5-Pad1)") (class "Default")
      (node (ref "J5") (pin "1") (pinfunction "1_1") (pintype "passive"))
      (node (ref "R8") (pin "2") (pinfunction "2_2") (pintype "passive"))
    )
    (net (code "28") (name "Net-(J5-Pad3)") (class "Default")
      (node (ref "J5") (pin "3") (pinfunction "3_3") (pintype "passive"))
      (node (ref "R28") (pin "1") (pinfunction "1_1") (pintype "passive"))
    )
    (net (code "29") (name "Net-(J6-CC1)") (class "Default")
      (node (ref "J6") (pin "A5") (pinfunction "CC1_A5") (pintype "passive"))
      (node (ref "R68") (pin "2") (pinfunction "2_2") (pintype "passive"))
    )
    (net (code "30") (name "Net-(J6-CC2)") (class "Default")
      (node (ref "J6") (pin "B5") (pinfunction "CC2_B5") (pintype "passive"))
      (node (ref "R69") (pin "2") (pinfunction "2_2") (pintype "passive"))
    )
    (net (code "31") (name "Net-(U1A-CFG_STRAP1)") (class "Default")
      (node (ref "R1") (pin "1") (pinfunction "1_1") (pintype "passive"))
      (node (ref "U1") (pin "21") (pinfunction "CFG_STRAP1_21") (pintype "passive"))
    )
    (net (code "32") (name "Net-(U1A-CFG_STRAP2)") (class "Default")
      (node (ref "R2") (pin "1") (pinfunction "1_1") (pintype "passive"))
      (node (ref "U1") (pin "22") (pinfunction "CFG_STRAP2_22") (pintype "passive"))
    )
    (net (code "33") (name "Net-(U1A-CFG_STRAP3)") (class "Default")
      (node (ref "R3") (pin "1") (pinfunction "1_1") (pintype "passive"))
      (node (ref "U1") (pin "23") (pinfunction "CFG_STRAP3_23") (pintype "passive"))
    )
    (net (code "34") (name "Net-(U1A-TESTEN)") (class "Default")
      (node (ref "R6") (pin "2") (pinfunction "2_2") (pintype "passive"))
      (node (ref "U1") (pin "24") (pinfunction "TESTEN_24") (pintype "passive"))
    )
    (net (code "35") (name "Net-(U1B-ATEST)") (class "Default")
      (node (ref "TP1") (pin "1") (pinfunction "1_1") (pintype "passive"))
      (node (ref "U1") (pin "96") (pinfunction "ATEST_96") (pintype "passive"))
    )
    (net (code "36") (name "Net-(U1B-RBIAS)") (class "Default")
      (node (ref "R11") (pin "2") (pinfunction "2_2") (pintype "passive"))
      (node (ref "U1") (pin "100") (pinfunction "RBIAS_100") (pintype "passive"))
    )
    (net (code "37") (name "Net-(U1B-TEST1)") (class "Default")
      (node (ref "R29") (pin "1") (pinfunction "1_1") (pintype "passive"))
      (node (ref "U1") (pin "63") (pinfunction "TEST1_63") (pintype "passive"))
    )
    (net (code "38") (name "Net-(U1B-TEST2)") (class "Default")
      (node (ref "R30") (pin "1") (pinfunction "1_1") (pintype "passive"))
      (node (ref "U1") (pin "64") (pinfunction "TEST2_64") (pintype "passive"))
    )
    (net (code "39") (name "Net-(U1B-TEST3)") (class "Default")
      (node (ref "R31") (pin "1") (pinfunction "1_1") (pintype "passive"))
      (node (ref "U1") (pin "65") (pinfunction "TEST3_65") (pintype "passive"))
    )
    (net (code "40") (name "Net-(U5-~{Y})") (class "Default")
      (node (ref "R16") (pin "2") (pinfunction "2_2") (pintype "passive"))
      (node (ref "U5") (pin "4") (pinfunction "~{Y}_4") (pintype "passive"))
    )
    (net (code "41") (name "Net-(U24-~{HOLD}{slash}SIO3)") (class "Default")
      (node (ref "J1") (pin "1") (pinfunction "1_1") (pintype "passive"))
      (node (ref "R17") (pin "1") (pinfunction "1_1") (pintype "passive"))
      (node (ref "R23") (pin "1") (pinfunction "1_1") (pintype "passive"))
      (node (ref "U24") (pin "7") (pinfunction "~{HOLD}/SIO3_7") (pintype "passive"))
    )
    (net (code "42") (name "Net-(U24-~{WP}{slash}SIO2)") (class "Default")
      (node (ref "R18") (pin "1") (pinfunction "1_1") (pintype "passive"))
      (node (ref "R21") (pin "1") (pinfunction "1_1") (pintype "passive"))
      (node (ref "U24") (pin "3") (pinfunction "~{WP}/SIO2_3") (pintype "passive"))
    )
    (net (code "43") (name "Net-(U25-~{Y})") (class "Default")
      (node (ref "R22") (pin "2") (pinfunction "2_2") (pintype "passive"))
      (node (ref "U25") (pin "4") (pinfunction "~{Y}_4") (pintype "passive"))
    )
    (net (code "44") (name "Net-(U26-~{Y})") (class "Default")
      (node (ref "D3") (pin "C") (pinfunction "C_C") (pintype "passive"))
      (node (ref "U26") (pin "4") (pinfunction "~{Y}_4") (pintype "passive"))
    )
    (net (code "45") (name "Net-(Y3-OUT)") (class "Default")
      (node (ref "R10") (pin "1") (pinfunction "1_1") (pintype "passive"))
      (node (ref "Y3") (pin "3") (pinfunction "OUT_3") (pintype "passive"))
    )
    (net (code "46") (name "SPI_CE_N{slash}CFG_NON_REM{slash}PF20") (class "Default")
      (node (ref "J3") (pin "5") (pinfunction "5_5") (pintype "passive"))
      (node (ref "U1") (pin "69") (pinfunction "SPI_CE_N/CFG_NON_REM/PF20_69") (pintype "passive"))
    )
    (net (code "47") (name "SPI_CLK{slash}PF21") (class "Default")
      (node (ref "J2") (pin "4") (pinfunction "4_4") (pintype "passive"))
      (node (ref "R19") (pin "1") (pinfunction "1_1") (pintype "passive"))
      (node (ref "U1") (pin "68") (pinfunction "SPI_CLK/PF21_68") (pintype "passive"))
      (node (ref "U24") (pin "6") (pinfunction "SCK_6") (pintype "passive"))
    )
    (net (code "48") (name "SPI_D1MISO{slash}PF23") (class "Default")
      (node (ref "R20") (pin "1") (pinfunction "1_1") (pintype "passive"))
      (node (ref "U1") (pin "71") (pinfunction "SPI_D1MISO/PF23_71") (pintype "passive"))
      (node (ref "U24") (pin "2") (pinfunction "SO/SIO1_2") (pintype "passive"))
    )
    (net (code "49") (name "SPI_MOSI{slash}D0{slash}CFG_BC_EN{slash}PF22") (class "Default")
      (node (ref "J3") (pin "2") (pinfunction "2_2") (pintype "passive"))
      (node (ref "U1") (pin "70") (pinfunction "SPI_MOSI/D0/CFG_BC_EN/PF22_70") (pintype "passive"))
    )
    (net (code "50") (name "USB2.0_DN_PORT1_N") (class "Default")
      (node (ref "U1") (pin "6") (pinfunction "USB2N_DM1/PRT_DIS_M1_6") (pintype "passive"))
    )
    (net (code "51") (name "USB2.0_DN_PORT1_P") (class "Default")
      (node (ref "U1") (pin "5") (pinfunction "USB2DN_DP1/PRT_DIS_P1_5") (pintype "passive"))
    )
    (net (code "52") (name "USB2.0_DN_PORT2_N") (class "Default")
      (node (ref "U1") (pin "15") (pinfunction "USB2DN_DM2/PRT_DIS_M2_15") (pintype "passive"))
    )
    (net (code "53") (name "USB2.0_DN_PORT2_P") (class "Default")
      (node (ref "U1") (pin "14") (pinfunction "USB2DN_DP2/PRT_DIS_P2_14") (pintype "passive"))
    )
    (net (code "54") (name "USB2.0_DN_PORT3_N") (class "Default")
      (node (ref "U1") (pin "28") (pinfunction "USB2N_DM3/PRT_DIS_M3_28") (pintype "passive"))
    )
    (net (code "55") (name "USB2.0_DN_PORT3_P") (class "Default")
      (node (ref "U1") (pin "27") (pinfunction "USB2DN_DP3/PRT_DIS_P3_27") (pintype "passive"))
    )
    (net (code "56") (name "USB2.0_DN_PORT4_N") (class "Default")
      (node (ref "U1") (pin "35") (pinfunction "USB2DN_DM4/PRT_DIS_M4_35") (pintype "passive"))
    )
    (net (code "57") (name "USB2.0_DN_PORT4_P") (class "Default")
      (node (ref "U1") (pin "34") (pinfunction "USB2DN_DP4/PRT_DIS_P4_34") (pintype "passive"))
    )
    (net (code "58") (name "USB2.0_DN_PORT5_N") (class "Default")
      (node (ref "U1") (pin "82") (pinfunction "USB2N_DM5/PRT_DIS_M5_82") (pintype "passive"))
    )
    (net (code "59") (name "USB2.0_DN_PORT5_P") (class "Default")
      (node (ref "U1") (pin "81") (pinfunction "USB2DN_DP5/PRT_DIS_P5_81") (pintype "passive"))
    )
    (net (code "60") (name "USB2.0_DN_PORT6_N") (class "Default")
      (node (ref "U1") (pin "41") (pinfunction "USB2DN_DM6/PRT_DIS_M6_41") (pintype "passive"))
    )
    (net (code "61") (name "USB2.0_DN_PORT6_P") (class "Default")
      (node (ref "U1") (pin "42") (pinfunction "USB2DN_DP6/PRT_DIS_P6_42") (pintype "passive"))
    )
    (net (code "62") (name "USB3.0_DN_PORT1_RX_N") (class "Default")
      (node (ref "U1") (pin "11") (pinfunction "USB3DN_RXDM1_11") (pintype "passive"))
    )
    (net (code "63") (name "USB3.0_DN_PORT1_RX_P") (class "Default")
      (node (ref "U1") (pin "10") (pinfunction "USB3DN_RXDP1_10") (pintype "passive"))
    )
    (net (code "64") (name "USB3.0_DN_PORT1_TX_N") (class "Default")
      (node (ref "U1") (pin "8") (pinfunction "USB3DN_TXDM1_8") (pintype "passive"))
    )
    (net (code "65") (name "USB3.0_DN_PORT1_TX_P") (class "Default")
      (node (ref "U1") (pin "7") (pinfunction "USB3DN_TXDP1_7") (pintype "passive"))
    )
    (net (code "66") (name "USB3.0_DN_PORT2_RX_N") (class "Default")
      (node (ref "U1") (pin "20") (pinfunction "USB3DN_RXDM2_20") (pintype "passive"))
    )
    (net (code "67") (name "USB3.0_DN_PORT2_RX_P") (class "Default")
      (node (ref "U1") (pin "19") (pinfunction "USB3DN_RXDP2_19") (pintype "passive"))
    )
    (net (code "68") (name "USB3.0_DN_PORT2_TX_N") (class "Default")
      (node (ref "U1") (pin "17") (pinfunction "USB3DN_TXDM2_17") (pintype "passive"))
    )
    (net (code "69") (name "USB3.0_DN_PORT2_TX_P") (class "Default")
      (node (ref "U1") (pin "16") (pinfunction "USB3DN_TXDP2_16") (pintype "passive"))
    )
    (net (code "70") (name "USB3.0_DN_PORT3_RX_N") (class "Default")
      (node (ref "U1") (pin "33") (pinfunction "USB3DN_RXDM3_33") (pintype "passive"))
    )
    (net (code "71") (name "USB3.0_DN_PORT3_RX_P") (class "Default")
      (node (ref "U1") (pin "32") (pinfunction "USB3DN_RXDP3_32") (pintype "passive"))
    )
    (net (code "72") (name "USB3.0_DN_PORT3_TX_N") (class "Default")
      (node (ref "U1") (pin "30") (pinfunction "USB3DN_TXDM3_30") (pintype "passive"))
    )
    (net (code "73") (name "USB3.0_DN_PORT3_TX_P") (class "Default")
      (node (ref "U1") (pin "29") (pinfunction "USB3DN_TXDP3_29") (pintype "passive"))
    )
    (net (code "74") (name "USB3.0_DN_PORT4_RX_N") (class "Default")
      (node (ref "U1") (pin "40") (pinfunction "USB3DN_RXDM4_40") (pintype "passive"))
    )
    (net (code "75") (name "USB3.0_DN_PORT4_RX_P") (class "Default")
      (node (ref "U1") (pin "39") (pinfunction "USB3DN_RXDP4_39") (pintype "passive"))
    )
    (net (code "76") (name "USB3.0_DN_PORT4_TX_N") (class "Default")
      (node (ref "U1") (pin "37") (pinfunction "USB3DN_TXDM4_37") (pintype "passive"))
    )
    (net (code "77") (name "USB3.0_DN_PORT4_TX_P") (class "Default")
      (node (ref "U1") (pin "36") (pinfunction "USB3DN_TXDP4_36") (pintype "passive"))
    )
    (net (code "78") (name "USB3.0_DN_PORT5_RX_N") (class "Default")
      (node (ref "U1") (pin "87") (pinfunction "USB3DN_RXDM5_87") (pintype "passive"))
    )
    (net (code "79") (name "USB3.0_DN_PORT5_RX_P") (class "Default")
      (node (ref "U1") (pin "86") (pinfunction "USB3DN_RXDP5_86") (pintype "passive"))
    )
    (net (code "80") (name "USB3.0_DN_PORT5_TX_N") (class "Default")
      (node (ref "U1") (pin "84") (pinfunction "USB3DN_TXDM5_84") (pintype "passive"))
    )
    (net (code "81") (name "USB3.0_DN_PORT5_TX_P") (class "Default")
      (node (ref "U1") (pin "83") (pinfunction "USB3DN_TXDP5_83") (pintype "passive"))
    )
    (net (code "82") (name "VBUS") (class "Default")
      (node (ref "C21") (pin "2") (pinfunction "2_2") (pintype "passive"))
      (node (ref "J6") (pin "A4") (pinfunction "VBUS_A_A4") (pintype "passive"))
      (node (ref "J6") (pin "A9") (pinfunction "VBUS_A_A9") (pintype "passive"))
      (node (ref "J6") (pin "B4") (pinfunction "VBUS_B_B4") (pintype "passive"))
      (node (ref "J6") (pin "B9") (pinfunction "VBUS_B_B9") (pintype "passive"))
      (node (ref "R4") (pin "2") (pinfunction "2_2") (pintype "passive"))
      (node (ref "U26") (pin "2") (pinfunction "A_2") (pintype "passive"))
    )
    (net (code "83") (name "unconnected-(J6-SBU1-PadA8)") (class "Default")
      (node (ref "J6") (pin "A8") (pinfunction "SBU1_A8") (pintype "passive+no_connect"))
    )
    (net (code "84") (name "unconnected-(J6-SBU2-PadB8)") (class "Default")
      (node (ref "J6") (pin "B8") (pinfunction "SBU2_B8") (pintype "passive+no_connect"))
    )
    (net (code "85") (name "unconnected-(U1A-NC-Pad4)") (class "Default")
      (node (ref "U1") (pin "4") (pinfunction "NC_4") (pintype "passive+no_connect"))
    )
    (net (code "86") (name "unconnected-(U1A-NC-Pad12)") (class "Default")
      (node (ref "U1") (pin "12") (pinfunction "NC_12") (pintype "passive+no_connect"))
    )
    (net (code "87") (name "unconnected-(U1A-NC-Pad13)") (class "Default")
      (node (ref "U1") (pin "13") (pinfunction "NC_13") (pintype "passive+no_connect"))
    )
    (net (code "88") (name "unconnected-(U1A-PF3-Pad44)") (class "Default")
      (node (ref "U1") (pin "44") (pinfunction "PF3_44") (pintype "passive+no_connect"))
    )
    (net (code "89") (name "unconnected-(U1A-PF4-Pad45)") (class "Default")
      (node (ref "U1") (pin "45") (pinfunction "PF4_45") (pintype "passive+no_connect"))
    )
    (net (code "90") (name "unconnected-(U1A-PF5-Pad46)") (class "Default")
      (node (ref "U1") (pin "46") (pinfunction "PF5_46") (pintype "passive+no_connect"))
    )
    (net (code "91") (name "unconnected-(U1A-PF6-Pad47)") (class "Default")
      (node (ref "U1") (pin "47") (pinfunction "PF6_47") (pintype "passive+no_connect"))
    )
    (net (code "92") (name "unconnected-(U1A-PF7-Pad48)") (class "Default")
      (node (ref "U1") (pin "48") (pinfunction "PF7_48") (pintype "passive+no_connect"))
    )
    (net (code "93") (name "unconnected-(U1A-PF8-Pad49)") (class "Default")
      (node (ref "U1") (pin "49") (pinfunction "PF8_49") (pintype "passive+no_connect"))
    )
    (net (code "94") (name "unconnected-(U1A-PF9-Pad50)") (class "Default")
      (node (ref "U1") (pin "50") (pinfunction "PF9_50") (pintype "passive+no_connect"))
    )
    (net (code "95") (name "unconnected-(U1A-PF10-Pad51)") (class "Default")
      (node (ref "U1") (pin "51") (pinfunction "PF10_51") (pintype "passive+no_connect"))
    )
    (net (code "96") (name "unconnected-(U1A-PF31-Pad3)") (class "Default")
      (node (ref "U1") (pin "3") (pinfunction "PF31_3") (pintype "passive+no_connect"))
    )
    (net (code "97") (name "unconnected-(U1B-NC-Pad80)") (class "Default")
      (node (ref "U1") (pin "80") (pinfunction "NC_80") (pintype "passive+no_connect"))
    )
    (net (code "98") (name "unconnected-(U1B-PF11-Pad52)") (class "Default")
      (node (ref "U1") (pin "52") (pinfunction "PF11_52") (pintype "passive+no_connect"))
    )
    (net (code "99") (name "unconnected-(U1B-PF12-Pad54)") (class "Default")
      (node (ref "U1") (pin "54") (pinfunction "PF12_54") (pintype "passive+no_connect"))
    )
    (net (code "100") (name "unconnected-(U1B-PF13-Pad56)") (class "Default")
      (node (ref "U1") (pin "56") (pinfunction "PF13_56") (pintype "passive+no_connect"))
    )
    (net (code "101") (name "unconnected-(U1B-PF14-Pad57)") (class "Default")
      (node (ref "U1") (pin "57") (pinfunction "PF14_57") (pintype "passive+no_connect"))
    )
    (net (code "102") (name "unconnected-(U1B-PF15-Pad58)") (class "Default")
      (node (ref "U1") (pin "58") (pinfunction "PF15_58") (pintype "passive+no_connect"))
    )
    (net (code "103") (name "unconnected-(U1B-PF16-Pad59)") (class "Default")
      (node (ref "U1") (pin "59") (pinfunction "PF16_59") (pintype "passive+no_connect"))
    )
    (net (code "104") (name "unconnected-(U1B-PF17-Pad60)") (class "Default")
      (node (ref "U1") (pin "60") (pinfunction "PF17_60") (pintype "passive+no_connect"))
    )
    (net (code "105") (name "unconnected-(U1B-PF18-Pad61)") (class "Default")
      (node (ref "U1") (pin "61") (pinfunction "PF18_61") (pintype "passive+no_connect"))
    )
    (net (code "106") (name "unconnected-(U1B-PF19-Pad66)") (class "Default")
      (node (ref "U1") (pin "66") (pinfunction "PF19_66") (pintype "passive+no_connect"))
    )
    (net (code "107") (name "unconnected-(U1B-PF26-Pad75)") (class "Default")
      (node (ref "U1") (pin "75") (pinfunction "PF26_75") (pintype "passive+no_connect"))
    )
    (net (code "108") (name "unconnected-(U1B-PF27-Pad76)") (class "Default")
      (node (ref "U1") (pin "76") (pinfunction "PF27_76") (pintype "passive+no_connect"))
    )
    (net (code "109") (name "unconnected-(U1B-PF28-Pad77)") (class "Default")
      (node (ref "U1") (pin "77") (pinfunction "PF28_77") (pintype "passive+no_connect"))
    )
    (net (code "110") (name "unconnected-(U1B-PF29-Pad74)") (class "Default")
      (node (ref "U1") (pin "74") (pinfunction "PF29_74") (pintype "passive+no_connect"))
    )
    (net (code "111") (name "unconnected-(U1B-SPI_D2{slash}PF24-Pad72)") (class "Default")
      (node (ref "U1") (pin "72") (pinfunction "SPI_D2/PF24_72") (pintype "passive+no_connect"))
    )
    (net (code "112") (name "unconnected-(U1B-SPI_D3{slash}PF25-Pad73)") (class "Default")
      (node (ref "U1") (pin "73") (pinfunction "SPI_D3/PF25_73") (pintype "passive+no_connect"))
    )
  )
)
